# Main.net
KiCad netlist of a schematic drawn in Altium Designer
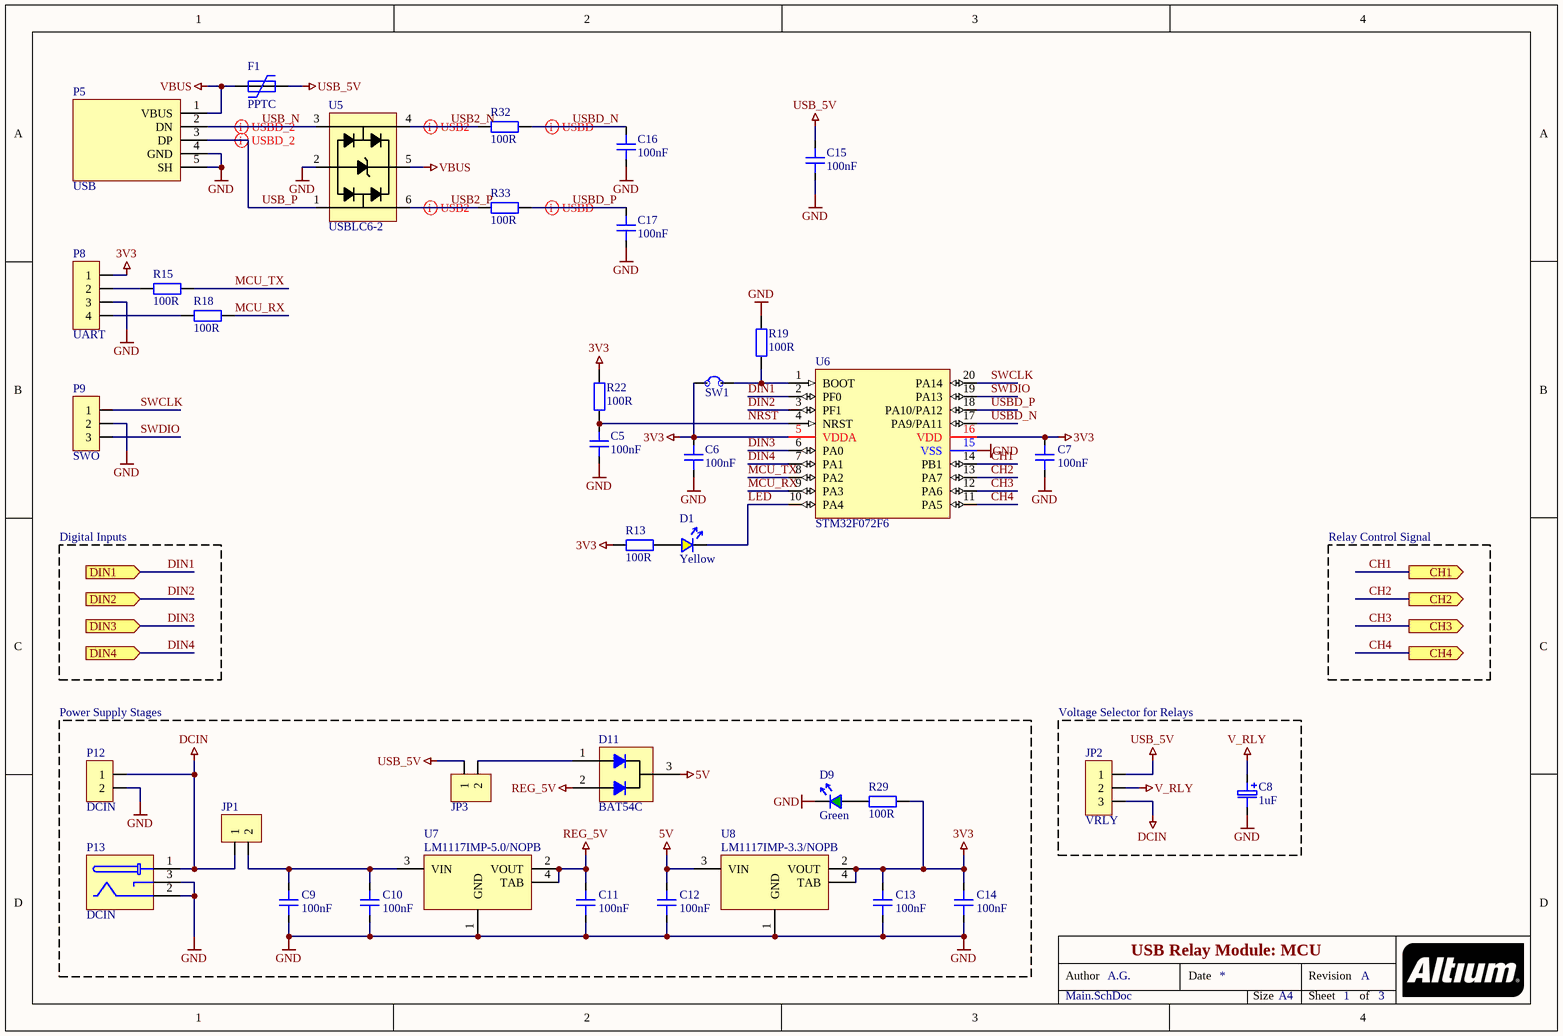
[diagram p0: Main.SchDoc]

(export (version "E")
  (design (tool "Eeschema 10.0.6"))
  (components
    (comp (ref "C5")
      (value "100nF")
      (footprint "AG.Passive:C0805")
      (description "Generic Capacitor")
      (fields (field (name "TOLERANCE") "20%"))
      (libsource (lib "AG.Generic") (part "C"))
    )
    (comp (ref "C6")
      (value "100nF")
      (footprint "AG.Passive:C0805")
      (description "Generic Capacitor")
      (fields (field (name "TOLERANCE") "20%"))
      (libsource (lib "AG.Generic") (part "C"))
    )
    (comp (ref "C7")
      (value "100nF")
      (footprint "AG.Passive:C0805")
      (description "Generic Capacitor")
      (fields (field (name "TOLERANCE") "20%"))
      (libsource (lib "AG.Generic") (part "C"))
    )
    (comp (ref "C8")
      (value "1uF")
      (footprint "AG.Passive:C_EL_6.3")
      (description "Generic Polarized Capacitor")
      (libsource (lib "AG.Generic") (part "CP"))
    )
    (comp (ref "C9")
      (value "100nF")
      (footprint "AG.Passive:C0805")
      (description "Generic Capacitor")
      (fields (field (name "TOLERANCE") "20%"))
      (libsource (lib "AG.Generic") (part "C"))
    )
    (comp (ref "C10")
      (value "100nF")
      (footprint "AG.Passive:C0805")
      (description "Generic Capacitor")
      (fields (field (name "TOLERANCE") "20%"))
      (libsource (lib "AG.Generic") (part "C"))
    )
    (comp (ref "C11")
      (value "100nF")
      (footprint "AG.Passive:C0805")
      (description "Generic Capacitor")
      (fields (field (name "TOLERANCE") "20%"))
      (libsource (lib "AG.Generic") (part "C"))
    )
    (comp (ref "C12")
      (value "100nF")
      (footprint "AG.Passive:C0805")
      (description "Generic Capacitor")
      (fields (field (name "TOLERANCE") "20%"))
      (libsource (lib "AG.Generic") (part "C"))
    )
    (comp (ref "C13")
      (value "100nF")
      (footprint "AG.Passive:C0805")
      (description "Generic Capacitor")
      (fields (field (name "TOLERANCE") "20%"))
      (libsource (lib "AG.Generic") (part "C"))
    )
    (comp (ref "C14")
      (value "100nF")
      (footprint "AG.Passive:C0805")
      (description "Generic Capacitor")
      (fields (field (name "TOLERANCE") "20%"))
      (libsource (lib "AG.Generic") (part "C"))
    )
    (comp (ref "C15")
      (value "100nF")
      (footprint "AG.Passive:C0805")
      (description "Generic Capacitor")
      (fields (field (name "TOLERANCE") "20%"))
      (libsource (lib "AG.Generic") (part "C"))
    )
    (comp (ref "C16")
      (value "100nF")
      (footprint "AG.Passive:C0805")
      (description "Generic Capacitor")
      (fields (field (name "TOLERANCE") "20%"))
      (libsource (lib "AG.Generic") (part "C"))
    )
    (comp (ref "C17")
      (value "100nF")
      (footprint "AG.Passive:C0805")
      (description "Generic Capacitor")
      (fields (field (name "TOLERANCE") "20%"))
      (libsource (lib "AG.Generic") (part "C"))
    )
    (comp (ref "D1")
      (value "Yellow")
      (footprint "AG.LED:LED1206")
      (description "Generic LED (Yellow)")
      (libsource (lib "AG.LED") (part "LED_YELLOW"))
    )
    (comp (ref "D9")
      (value "Green")
      (footprint "AG.LED:LED1206")
      (description "Generic LED (Green)")
      (libsource (lib "AG.LED") (part "LED_GREEN"))
    )
    (comp (ref "D11")
      (value "BAT54C")
      (footprint "SOT-23-127P600-8N")
      (description "DIODE ARRAY SCHOTTKY COMM CATH 30V 0.2A SOT-23")
      (fields (field (name "PARTNO") "BAT54C-FDICT-ND") (field (name "MANUFACTURER") "Diodes Incorporated"))
      (libsource (lib "AG") (part "BAT54C"))
    )
    (comp (ref "F1")
      (value "PPTC")
      (footprint "AG.Misc:MF-MSMF110/16-2")
      (description "PolyFuse (LittleFuse)")
      (libsource (lib "AG.Misc") (part "PPTC"))
    )
    (comp (ref "JP1")
      (value "PINHDR_2x1")
      (footprint "AG.Connectors:HEADER-2.54-2P1")
      (description "Generic Pin Header 2x1")
      (libsource (lib "") (part "PINHDR_2x1_1"))
    )
    (comp (ref "JP2")
      (value "VRLY")
      (footprint "AG.Connectors:HEADER-2.54-3P1")
      (description "Generic Pin Header 3x1")
      (libsource (lib "AG.Connectors") (part "PINHDR_3x1"))
    )
    (comp (ref "JP3")
      (value "~")
      (footprint "AG.Connectors:HEADER-2.54-2P1")
      (description "Generic Pin Header 2x1")
      (libsource (lib "") (part "PINHDR_2x1_2"))
    )
    (comp (ref "P5")
      (value "USB")
      (footprint "UJ2-BH-2-TH")
      (description "CONN RCPT USB2.0 TYPEB 4POS R/A")
      (fields (field (name "PARTNO") "102-5884-ND") (field (name "MANUFACTURER") "CUI Devices"))
      (libsource (lib "AG.Connectors") (part "UJ2-BH-2-TH"))
    )
    (comp (ref "P8")
      (value "UART")
      (footprint "AG.Connectors:HEADER-2.54-4P1")
      (description "Generic Pin Header 4x1")
      (libsource (lib "AG.Connectors") (part "PINHDR_4x1"))
    )
    (comp (ref "P9")
      (value "SWO")
      (footprint "AG.Connectors:HEADER-2.54-3P1")
      (description "Generic Pin Header 3x1")
      (libsource (lib "AG.Connectors") (part "PINHDR_3x1"))
    )
    (comp (ref "P12")
      (value "DCIN")
      (footprint "AG.Connectors:HEADER-2.54-2P1")
      (description "Generic Pin Header 2x1")
      (libsource (lib "AG.Connectors") (part "PINHDR_2x1"))
    )
    (comp (ref "P13")
      (value "DCIN")
      (footprint "CON JACK PWR 2.5mm PJ-002BH - duplicate")
      (description "CONN PWR JACK 2.5X5.5MM SOLDER")
      (fields (field (name "MANUFACTURER") "CUI Devices") (field (name "PARTNO") "CP-002BH-ND"))
      (libsource (lib "AG.Connectors") (part "PJ-002BH"))
    )
    (comp (ref "R13")
      (value "100R")
      (footprint "AG.Passive:R0805")
      (description "Generic Resistor")
      (fields (field (name "TOLERANCE") "1%"))
      (libsource (lib "AG.Generic") (part "R"))
    )
    (comp (ref "R15")
      (value "100R")
      (footprint "AG.Passive:R0805")
      (description "Generic Resistor")
      (fields (field (name "TOLERANCE") "1%"))
      (libsource (lib "AG.Generic") (part "R"))
    )
    (comp (ref "R18")
      (value "100R")
      (footprint "AG.Passive:R0805")
      (description "Generic Resistor")
      (fields (field (name "TOLERANCE") "1%"))
      (libsource (lib "AG.Generic") (part "R"))
    )
    (comp (ref "R19")
      (value "100R")
      (footprint "AG.Passive:R0805")
      (description "Generic Resistor")
      (fields (field (name "TOLERANCE") "1%"))
      (libsource (lib "AG.Generic") (part "R"))
    )
    (comp (ref "R22")
      (value "100R")
      (footprint "AG.Passive:R0805")
      (description "Generic Resistor")
      (fields (field (name "TOLERANCE") "1%"))
      (libsource (lib "AG.Generic") (part "R"))
    )
    (comp (ref "R29")
      (value "100R")
      (footprint "AG.Passive:R0805")
      (description "Generic Resistor")
      (fields (field (name "TOLERANCE") "1%"))
      (libsource (lib "AG.Generic") (part "R"))
    )
    (comp (ref "R32")
      (value "100R")
      (footprint "AG.Passive:R0805")
      (description "Generic Resistor")
      (fields (field (name "TOLERANCE") "1%"))
      (libsource (lib "AG.Generic") (part "R"))
    )
    (comp (ref "R33")
      (value "100R")
      (footprint "AG.Passive:R0805")
      (description "Generic Resistor")
      (fields (field (name "TOLERANCE") "1%"))
      (libsource (lib "AG.Generic") (part "R"))
    )
    (comp (ref "SW1")
      (value "SolderBridge-1")
      (footprint "AG.Passive:R0805")
      (description "PCB Solder Bridge")
      (libsource (lib "AG.Misc") (part "SolderBridge-1"))
    )
    (comp (ref "U5")
      (value "USBLC6-2")
      (footprint "AG:USBLC6-2-SOT95P280X145-6N")
      (description "Low capacitance USB ESD protection")
      (libsource (lib "AG") (part "USBLC6-2"))
    )
    (comp (ref "U6")
      (value "STM32F072F6")
      (footprint "TSSOP-20")
      (description "IC MCU 32BIT 32KB FLASH 20TSSOP")
      (fields (field (name "PARTNO") "497-17354-1-ND"))
      (libsource (lib "AG.MCU") (part "STM32F072F6P6"))
    )
    (comp (ref "U7")
      (value "LM1117IMP-5.0/NOPB")
      (footprint "SOT-223_127P600-8N")
      (description "IC REG LINEAR 5V 800MA SOT223")
      (fields
        (field (name "PARTNO") "LM1117IMP-5.0/NOPBCT-ND")
        (field (name "MANUFACTURER") "Texas Instruments")
      )
      (libsource (lib "AG") (part "LM1117IMP-5.0/NOPB"))
    )
    (comp (ref "U8")
      (value "LM1117IMP-3.3/NOPB")
      (footprint "SOT-223_127P600-8N")
      (description "IC REG LINEAR 3.3V 800MA SOT223")
      (fields
        (field (name "PARTNO") "LM1117IMP-3.3/NOPBCT-ND")
        (field (name "MANUFACTURER") "Texas Instruments")
      )
      (libsource (lib "AG") (part "LM1117IMP-3.3/NOPB"))
    )
  )
  (nets
    (net (code "1") (name "/CH1") (class "Default")
      (node (ref "U6") (pin "14") (pinfunction "PB1_14") (pintype "bidirectional"))
    )
    (net (code "2") (name "/CH2") (class "Default")
      (node (ref "U6") (pin "13") (pinfunction "PA7_13") (pintype "bidirectional"))
    )
    (net (code "3") (name "/CH3") (class "Default")
      (node (ref "U6") (pin "12") (pinfunction "PA6_12") (pintype "bidirectional"))
    )
    (net (code "4") (name "/CH4") (class "Default")
      (node (ref "U6") (pin "11") (pinfunction "PA5_11") (pintype "bidirectional"))
    )
    (net (code "5") (name "/DIN1") (class "Default")
      (node (ref "U6") (pin "2") (pinfunction "PF0_2") (pintype "bidirectional"))
    )
    (net (code "6") (name "/DIN2") (class "Default")
      (node (ref "U6") (pin "3") (pinfunction "PF1_3") (pintype "bidirectional"))
    )
    (net (code "7") (name "/DIN3") (class "Default")
      (node (ref "U6") (pin "6") (pinfunction "PA0_6") (pintype "bidirectional"))
    )
    (net (code "8") (name "/DIN4") (class "Default")
      (node (ref "U6") (pin "7") (pinfunction "PA1_7") (pintype "bidirectional"))
    )
    (net (code "9") (name "/LED") (class "Default")
      (node (ref "D1") (pin "2") (pinfunction "C_2") (pintype "passive"))
      (node (ref "U6") (pin "10") (pinfunction "PA4_10") (pintype "bidirectional"))
    )
    (net (code "10") (name "/MCU_RX") (class "Default")
      (node (ref "R18") (pin "2") (pintype "passive"))
      (node (ref "U6") (pin "9") (pinfunction "PA3_9") (pintype "bidirectional"))
    )
    (net (code "11") (name "/MCU_TX") (class "Default")
      (node (ref "R15") (pin "2") (pintype "passive"))
      (node (ref "U6") (pin "8") (pinfunction "PA2_8") (pintype "bidirectional"))
    )
    (net (code "12") (name "/NRST") (class "Default")
      (node (ref "C5") (pin "2") (pinfunction "2_2") (pintype "passive"))
      (node (ref "R22") (pin "2") (pintype "passive"))
      (node (ref "U6") (pin "4") (pinfunction "NRST_4") (pintype "input"))
    )
    (net (code "13") (name "/SWCLK") (class "Default")
      (node (ref "P9") (pin "1") (pinfunction "1_1") (pintype "passive"))
      (node (ref "U6") (pin "20") (pinfunction "PA14_20") (pintype "bidirectional"))
    )
    (net (code "14") (name "/SWDIO") (class "Default")
      (node (ref "P9") (pin "3") (pinfunction "3_3") (pintype "passive"))
      (node (ref "U6") (pin "19") (pinfunction "PA13_19") (pintype "bidirectional"))
    )
    (net (code "15") (name "/USB2_N") (class "Default")
      (node (ref "R32") (pin "1") (pintype "passive"))
      (node (ref "U5") (pin "4") (pinfunction "4_4") (pintype "passive"))
    )
    (net (code "16") (name "/USB2_P") (class "Default")
      (node (ref "R33") (pin "1") (pintype "passive"))
      (node (ref "U5") (pin "6") (pinfunction "6_6") (pintype "passive"))
    )
    (net (code "17") (name "/USBD_N") (class "Default")
      (node (ref "C16") (pin "2") (pinfunction "2_2") (pintype "passive"))
      (node (ref "R32") (pin "2") (pintype "passive"))
      (node (ref "U6") (pin "17") (pinfunction "PA9/PA11_17") (pintype "bidirectional"))
    )
    (net (code "18") (name "/USBD_P") (class "Default")
      (node (ref "C17") (pin "2") (pinfunction "2_2") (pintype "passive"))
      (node (ref "R33") (pin "2") (pintype "passive"))
      (node (ref "U6") (pin "18") (pinfunction "PA10/PA12_18") (pintype "bidirectional"))
    )
    (net (code "19") (name "/USB_N") (class "Default")
      (node (ref "P5") (pin "2") (pinfunction "DN_2") (pintype "passive"))
      (node (ref "U5") (pin "3") (pinfunction "3_3") (pintype "passive"))
    )
    (net (code "20") (name "/USB_P") (class "Default")
      (node (ref "P5") (pin "3") (pinfunction "DP_3") (pintype "passive"))
      (node (ref "U5") (pin "1") (pinfunction "1_1") (pintype "passive"))
    )
    (net (code "21") (name "3V3") (class "Default")
      (node (ref "C13") (pin "2") (pinfunction "2_2") (pintype "passive"))
      (node (ref "C14") (pin "2") (pinfunction "2_2") (pintype "passive"))
      (node (ref "C6") (pin "2") (pinfunction "2_2") (pintype "passive"))
      (node (ref "C7") (pin "2") (pinfunction "2_2") (pintype "passive"))
      (node (ref "P8") (pin "1") (pinfunction "1_1") (pintype "passive"))
      (node (ref "R13") (pin "2") (pintype "passive"))
      (node (ref "R22") (pin "1") (pintype "passive"))
      (node (ref "R29") (pin "2") (pintype "passive"))
      (node (ref "SW1") (pin "1") (pinfunction "1_1") (pintype "passive"))
      (node (ref "U6") (pin "16") (pinfunction "VDD_16") (pintype "power_in"))
      (node (ref "U6") (pin "5") (pinfunction "VDDA_5") (pintype "power_in"))
      (node (ref "U8") (pin "2") (pinfunction "VOUT_2") (pintype "passive"))
      (node (ref "U8") (pin "4") (pinfunction "TAB_4") (pintype "passive"))
    )
    (net (code "22") (name "5V") (class "Default")
      (node (ref "C12") (pin "2") (pinfunction "2_2") (pintype "passive"))
      (node (ref "D11") (pin "3") (pinfunction "C_3") (pintype "passive"))
      (node (ref "U8") (pin "3") (pinfunction "VIN_3") (pintype "passive"))
    )
    (net (code "23") (name "DCIN") (class "Default")
      (node (ref "JP1") (pin "1") (pinfunction "1_1") (pintype "passive"))
      (node (ref "JP2") (pin "3") (pinfunction "3_3") (pintype "passive"))
      (node (ref "P12") (pin "1") (pinfunction "1_1") (pintype "passive"))
      (node (ref "P13") (pin "1") (pinfunction "1_1") (pintype "passive"))
    )
    (net (code "24") (name "GND") (class "Default")
      (node (ref "C10") (pin "1") (pinfunction "1_1") (pintype "passive"))
      (node (ref "C11") (pin "1") (pinfunction "1_1") (pintype "passive"))
      (node (ref "C12") (pin "1") (pinfunction "1_1") (pintype "passive"))
      (node (ref "C13") (pin "1") (pinfunction "1_1") (pintype "passive"))
      (node (ref "C14") (pin "1") (pinfunction "1_1") (pintype "passive"))
      (node (ref "C15") (pin "1") (pinfunction "1_1") (pintype "passive"))
      (node (ref "C16") (pin "1") (pinfunction "1_1") (pintype "passive"))
      (node (ref "C17") (pin "1") (pinfunction "1_1") (pintype "passive"))
      (node (ref "C5") (pin "1") (pinfunction "1_1") (pintype "passive"))
      (node (ref "C6") (pin "1") (pinfunction "1_1") (pintype "passive"))
      (node (ref "C7") (pin "1") (pinfunction "1_1") (pintype "passive"))
      (node (ref "C8") (pin "2") (pinfunction "2_2") (pintype "power_in"))
      (node (ref "C9") (pin "1") (pinfunction "1_1") (pintype "passive"))
      (node (ref "D9") (pin "2") (pinfunction "C_2") (pintype "passive"))
      (node (ref "P12") (pin "2") (pinfunction "2_2") (pintype "passive"))
      (node (ref "P13") (pin "2") (pinfunction "2_2") (pintype "passive"))
      (node (ref "P13") (pin "3") (pinfunction "3_3") (pintype "passive"))
      (node (ref "P5") (pin "4") (pinfunction "GND_4") (pintype "passive"))
      (node (ref "P5") (pin "5") (pinfunction "SH_5") (pintype "passive"))
      (node (ref "P8") (pin "3") (pinfunction "3_3") (pintype "passive"))
      (node (ref "P9") (pin "2") (pinfunction "2_2") (pintype "passive"))
      (node (ref "R19") (pin "1") (pintype "passive"))
      (node (ref "U5") (pin "2") (pinfunction "2_2") (pintype "passive"))
      (node (ref "U6") (pin "15") (pinfunction "VSS_15") (pintype "power_in"))
      (node (ref "U7") (pin "1") (pinfunction "GND_1") (pintype "passive"))
      (node (ref "U8") (pin "1") (pinfunction "GND_1") (pintype "passive"))
    )
    (net (code "25") (name "Net-(D1-A)") (class "Default")
      (node (ref "D1") (pin "1") (pinfunction "A_1") (pintype "passive"))
      (node (ref "R13") (pin "1") (pintype "passive"))
    )
    (net (code "26") (name "Net-(D9-A)") (class "Default")
      (node (ref "D9") (pin "1") (pinfunction "A_1") (pintype "passive"))
      (node (ref "R29") (pin "1") (pintype "passive"))
    )
    (net (code "27") (name "Net-(D11-A1)") (class "Default")
      (node (ref "D11") (pin "1") (pinfunction "A1_1") (pintype "passive"))
      (node (ref "JP3") (pin "2") (pinfunction "2_2") (pintype "passive"))
    )
    (net (code "28") (name "Net-(P8-Pad2)") (class "Default")
      (node (ref "P8") (pin "2") (pinfunction "2_2") (pintype "passive"))
      (node (ref "R15") (pin "1") (pintype "passive"))
    )
    (net (code "29") (name "Net-(P8-Pad4)") (class "Default")
      (node (ref "P8") (pin "4") (pinfunction "4_4") (pintype "passive"))
      (node (ref "R18") (pin "1") (pintype "passive"))
    )
    (net (code "30") (name "Net-(U6-BOOT)") (class "Default")
      (node (ref "R19") (pin "2") (pintype "passive"))
      (node (ref "SW1") (pin "2") (pinfunction "2_2") (pintype "passive"))
      (node (ref "U6") (pin "1") (pinfunction "BOOT_1") (pintype "input"))
    )
    (net (code "31") (name "Net-(U7-VIN)") (class "Default")
      (node (ref "C10") (pin "2") (pinfunction "2_2") (pintype "passive"))
      (node (ref "C9") (pin "2") (pinfunction "2_2") (pintype "passive"))
      (node (ref "JP1") (pin "2") (pinfunction "2_2") (pintype "passive"))
      (node (ref "U7") (pin "3") (pinfunction "VIN_3") (pintype "passive"))
    )
    (net (code "32") (name "REG_5V") (class "Default")
      (node (ref "C11") (pin "2") (pinfunction "2_2") (pintype "passive"))
      (node (ref "D11") (pin "2") (pinfunction "A2_2") (pintype "passive"))
      (node (ref "U7") (pin "2") (pinfunction "VOUT_2") (pintype "passive"))
      (node (ref "U7") (pin "4") (pinfunction "TAB_4") (pintype "passive"))
    )
    (net (code "33") (name "USB_5V") (class "Default")
      (node (ref "C15") (pin "2") (pinfunction "2_2") (pintype "passive"))
      (node (ref "F1") (pin "1") (pinfunction "1_1") (pintype "passive"))
      (node (ref "JP2") (pin "1") (pinfunction "1_1") (pintype "passive"))
      (node (ref "JP3") (pin "1") (pinfunction "1_1") (pintype "passive"))
    )
    (net (code "34") (name "VBUS") (class "Default")
      (node (ref "F1") (pin "2") (pinfunction "2_2") (pintype "passive"))
      (node (ref "P5") (pin "1") (pinfunction "VBUS_1") (pintype "passive"))
      (node (ref "U5") (pin "5") (pinfunction "5_5") (pintype "passive"))
    )
    (net (code "35") (name "V_RLY") (class "Default")
      (node (ref "C8") (pin "1") (pinfunction "1_1") (pintype "power_in"))
      (node (ref "JP2") (pin "2") (pinfunction "2_2") (pintype "passive"))
    )
  )
)
